# LS013B7DH03_TFT_Module.net
KiCad netlist of a schematic drawn in EAGLE
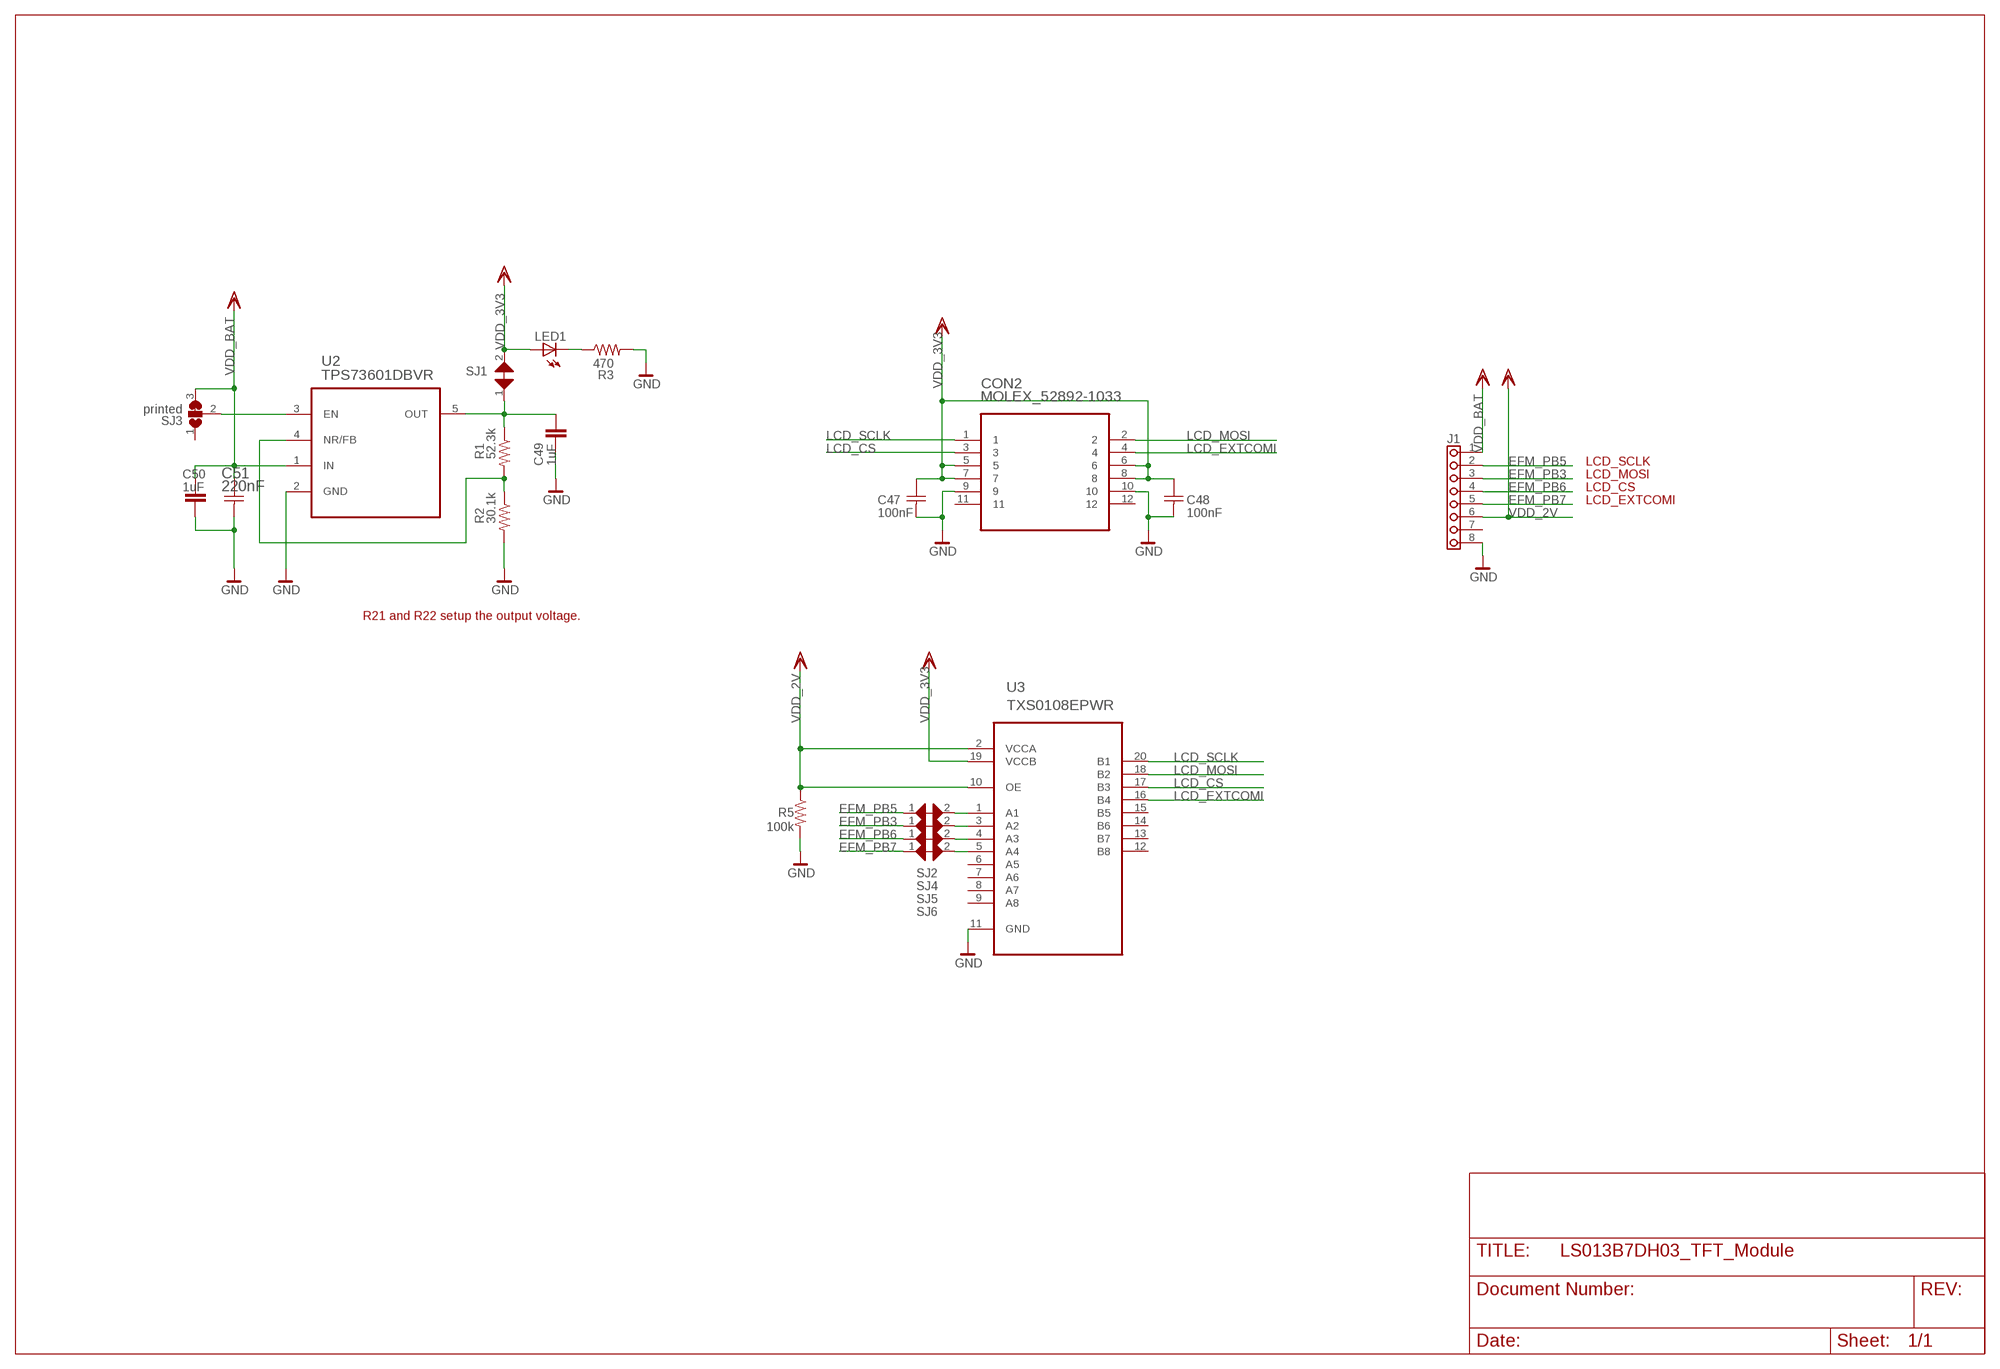
[diagram p0: schematic, sheet 1]

(export (version "E")
  (design (tool "Eeschema 10.0.6"))
  (components
    (comp (ref "C47")
      (value "100nF")
      (footprint "eagle-import:CAPC1005X60N")
      (libsource (lib "eagle-import") (part "CAP_GRM15"))
    )
    (comp (ref "C48")
      (value "100nF")
      (footprint "eagle-import:CAPC1005X60N")
      (libsource (lib "eagle-import") (part "CAP_GRM15"))
    )
    (comp (ref "C49")
      (value "1uF")
      (footprint "eagle-import:0603")
      (libsource (lib "eagle-import") (part "CAP-SMD0603"))
    )
    (comp (ref "C50")
      (value "1uF")
      (footprint "eagle-import:0603")
      (libsource (lib "eagle-import") (part "CAP-SMD0603"))
    )
    (comp (ref "C51")
      (value "220nF")
      (footprint "eagle-import:CAPC1005X60N")
      (libsource (lib "eagle-import") (part "CAP_GRM15"))
    )
    (comp (ref "CON2")
      (value "MOLEX_52892-1033")
      (footprint "eagle-import:MOLEX_52892-1095")
      (libsource (lib "eagle-import") (part "MOLEX_52892-1033_FPC"))
    )
    (comp (ref "J1")
      (value "PIN8S")
      (footprint "eagle-import:PIN8S")
      (libsource (lib "eagle-import") (part "PIN8S"))
    )
    (comp (ref "LED1")
      (value "LED0603")
      (footprint "eagle-import:LED-0603")
      (libsource (lib "eagle-import") (part "LED0603"))
    )
    (comp (ref "R1")
      (value "52.3k")
      (footprint "eagle-import:R0402")
      (libsource (lib "eagle-import") (part "R-US_R0402"))
    )
    (comp (ref "R2")
      (value "30.1k")
      (footprint "eagle-import:R0402")
      (libsource (lib "eagle-import") (part "R-US_R0402"))
    )
    (comp (ref "R3")
      (value "470")
      (footprint "eagle-import:R0402")
      (libsource (lib "eagle-import") (part "R-US_R0402"))
    )
    (comp (ref "R5")
      (value "100k")
      (footprint "eagle-import:R0402")
      (libsource (lib "eagle-import") (part "R-US_R0402"))
    )
    (comp (ref "SJ1")
      (value "printed")
      (footprint "eagle-import:JUMPER_SMD_MICRO_SHORT")
      (libsource (lib "eagle-import") (part "JUMPER_SMD_MICRO_SHORT"))
    )
    (comp (ref "SJ2")
      (value "printed")
      (footprint "eagle-import:JUMPER_SMD_MICRO_SHORT")
      (libsource (lib "eagle-import") (part "JUMPER_SMD_MICRO_SHORT"))
    )
    (comp (ref "SJ3")
      (value "printed")
      (footprint "eagle-import:JUMPER_SMD_SJ2A")
      (libsource (lib "eagle-import") (part "JUMPER_SMD_3A"))
    )
    (comp (ref "SJ4")
      (value "printed")
      (footprint "eagle-import:JUMPER_SMD_MICRO_SHORT")
      (libsource (lib "eagle-import") (part "JUMPER_SMD_MICRO_SHORT"))
    )
    (comp (ref "SJ5")
      (value "printed")
      (footprint "eagle-import:JUMPER_SMD_MICRO_SHORT")
      (libsource (lib "eagle-import") (part "JUMPER_SMD_MICRO_SHORT"))
    )
    (comp (ref "SJ6")
      (value "printed")
      (footprint "eagle-import:JUMPER_SMD_MICRO_SHORT")
      (libsource (lib "eagle-import") (part "JUMPER_SMD_MICRO_SHORT"))
    )
    (comp (ref "U2")
      (value "TPS73601DBVR")
      (footprint "eagle-import:SOT95P280X145-5N")
      (libsource (lib "eagle-import") (part "TPS73601DBVR"))
    )
    (comp (ref "U3")
      (value "TXS0108EPWR")
      (footprint "eagle-import:SOP65P640X120-20N")
      (libsource (lib "eagle-import") (part "TXB0108PWR"))
    )
  )
  (nets
    (net (code "1") (name "/EFM_PB3") (class "Default")
      (node (ref "J1") (pin "3") (pinfunction "3_3") (pintype "passive"))
      (node (ref "SJ4") (pin "1") (pinfunction "1_1") (pintype "passive"))
    )
    (net (code "2") (name "/EFM_PB5") (class "Default")
      (node (ref "J1") (pin "2") (pinfunction "2_2") (pintype "passive"))
      (node (ref "SJ2") (pin "1") (pinfunction "1_1") (pintype "passive"))
    )
    (net (code "3") (name "/EFM_PB6") (class "Default")
      (node (ref "J1") (pin "4") (pinfunction "4_4") (pintype "passive"))
      (node (ref "SJ5") (pin "1") (pinfunction "1_1") (pintype "passive"))
    )
    (net (code "4") (name "/EFM_PB7") (class "Default")
      (node (ref "J1") (pin "5") (pinfunction "5_5") (pintype "passive"))
      (node (ref "SJ6") (pin "1") (pinfunction "1_1") (pintype "passive"))
    )
    (net (code "5") (name "/LCD_CS") (class "Default")
      (node (ref "CON2") (pin "3") (pinfunction "3_3") (pintype "passive"))
      (node (ref "U3") (pin "17") (pinfunction "B3_17") (pintype "bidirectional"))
    )
    (net (code "6") (name "/LCD_EXTCOMI") (class "Default")
      (node (ref "CON2") (pin "4") (pinfunction "4_4") (pintype "passive"))
      (node (ref "U3") (pin "16") (pinfunction "B4_16") (pintype "bidirectional"))
    )
    (net (code "7") (name "/LCD_MOSI") (class "Default")
      (node (ref "CON2") (pin "2") (pinfunction "2_2") (pintype "passive"))
      (node (ref "U3") (pin "18") (pinfunction "B2_18") (pintype "bidirectional"))
    )
    (net (code "8") (name "/LCD_SCLK") (class "Default")
      (node (ref "CON2") (pin "1") (pinfunction "1_1") (pintype "passive"))
      (node (ref "U3") (pin "20") (pinfunction "B1_20") (pintype "bidirectional"))
    )
    (net (code "9") (name "GND") (class "Default")
      (node (ref "C47") (pin "2") (pinfunction "C2_2") (pintype "passive"))
      (node (ref "C48") (pin "2") (pinfunction "C2_2") (pintype "passive"))
      (node (ref "C49") (pin "1") (pinfunction "1_1") (pintype "passive"))
      (node (ref "C50") (pin "1") (pinfunction "1_1") (pintype "passive"))
      (node (ref "C51") (pin "2") (pinfunction "C2_2") (pintype "passive"))
      (node (ref "CON2") (pin "10") (pinfunction "10_10") (pintype "passive"))
      (node (ref "CON2") (pin "9") (pinfunction "9_9") (pintype "passive"))
      (node (ref "J1") (pin "8") (pinfunction "8_8") (pintype "passive"))
      (node (ref "R2") (pin "2") (pinfunction "2_2") (pintype "passive"))
      (node (ref "R3") (pin "2") (pinfunction "2_2") (pintype "passive"))
      (node (ref "R5") (pin "2") (pinfunction "2_2") (pintype "passive"))
      (node (ref "U2") (pin "2") (pinfunction "GND_2") (pintype "passive"))
      (node (ref "U3") (pin "11") (pinfunction "GND_11") (pintype "passive"))
    )
    (net (code "10") (name "Net-(LED1-PadC)") (class "Default")
      (node (ref "LED1") (pin "C") (pinfunction "C_C") (pintype "passive"))
      (node (ref "R3") (pin "1") (pinfunction "1_1") (pintype "passive"))
    )
    (net (code "11") (name "Net-(U2-EN)") (class "Default")
      (node (ref "SJ3") (pin "2") (pinfunction "2_2") (pintype "passive"))
      (node (ref "U2") (pin "3") (pinfunction "EN_3") (pintype "input"))
    )
    (net (code "12") (name "Net-(U2-NR{slash}FB)") (class "Default")
      (node (ref "R1") (pin "2") (pinfunction "2_2") (pintype "passive"))
      (node (ref "R2") (pin "1") (pinfunction "1_1") (pintype "passive"))
      (node (ref "U2") (pin "4") (pinfunction "NR/FB_4") (pintype "input"))
    )
    (net (code "13") (name "Net-(U2-OUT)") (class "Default")
      (node (ref "C49") (pin "2") (pinfunction "2_2") (pintype "passive"))
      (node (ref "R1") (pin "1") (pinfunction "1_1") (pintype "passive"))
      (node (ref "SJ1") (pin "1") (pinfunction "1_1") (pintype "passive"))
      (node (ref "U2") (pin "5") (pinfunction "OUT_5") (pintype "power_in"))
    )
    (net (code "14") (name "Net-(U3-A1)") (class "Default")
      (node (ref "SJ2") (pin "2") (pinfunction "2_2") (pintype "passive"))
      (node (ref "U3") (pin "1") (pinfunction "A1_1") (pintype "bidirectional"))
    )
    (net (code "15") (name "Net-(U3-A2)") (class "Default")
      (node (ref "SJ4") (pin "2") (pinfunction "2_2") (pintype "passive"))
      (node (ref "U3") (pin "3") (pinfunction "A2_3") (pintype "bidirectional"))
    )
    (net (code "16") (name "Net-(U3-A3)") (class "Default")
      (node (ref "SJ5") (pin "2") (pinfunction "2_2") (pintype "passive"))
      (node (ref "U3") (pin "4") (pinfunction "A3_4") (pintype "bidirectional"))
    )
    (net (code "17") (name "Net-(U3-A4)") (class "Default")
      (node (ref "SJ6") (pin "2") (pinfunction "2_2") (pintype "passive"))
      (node (ref "U3") (pin "5") (pinfunction "A4_5") (pintype "bidirectional"))
    )
    (net (code "18") (name "VDD_2V") (class "Default")
      (node (ref "J1") (pin "6") (pinfunction "6_6") (pintype "passive"))
      (node (ref "R5") (pin "1") (pinfunction "1_1") (pintype "passive"))
      (node (ref "U3") (pin "10") (pinfunction "OE_10") (pintype "input"))
      (node (ref "U3") (pin "2") (pinfunction "VCCA_2") (pintype "power_in"))
    )
    (net (code "19") (name "VDD_3V3") (class "Default")
      (node (ref "C47") (pin "1") (pinfunction "C1_1") (pintype "passive"))
      (node (ref "C48") (pin "1") (pinfunction "C1_1") (pintype "passive"))
      (node (ref "CON2") (pin "5") (pinfunction "5_5") (pintype "passive"))
      (node (ref "CON2") (pin "6") (pinfunction "6_6") (pintype "passive"))
      (node (ref "CON2") (pin "7") (pinfunction "7_7") (pintype "passive"))
      (node (ref "CON2") (pin "8") (pinfunction "8_8") (pintype "passive"))
      (node (ref "LED1") (pin "A") (pinfunction "A_A") (pintype "passive"))
      (node (ref "SJ1") (pin "2") (pinfunction "2_2") (pintype "passive"))
      (node (ref "U3") (pin "19") (pinfunction "VCCB_19") (pintype "power_in"))
    )
    (net (code "20") (name "VDD_BAT") (class "Default")
      (node (ref "C50") (pin "2") (pinfunction "2_2") (pintype "passive"))
      (node (ref "C51") (pin "1") (pinfunction "C1_1") (pintype "passive"))
      (node (ref "J1") (pin "1") (pinfunction "1_1") (pintype "passive"))
      (node (ref "SJ3") (pin "3") (pinfunction "3_3") (pintype "passive"))
      (node (ref "U2") (pin "1") (pinfunction "IN_1") (pintype "power_in"))
    )
    (net (code "21") (name "unconnected-(CON2-Pad11)") (class "Default")
      (node (ref "CON2") (pin "11") (pinfunction "11_11") (pintype "passive"))
    )
    (net (code "22") (name "unconnected-(CON2-Pad12)") (class "Default")
      (node (ref "CON2") (pin "12") (pinfunction "12_12") (pintype "passive"))
    )
    (net (code "23") (name "unconnected-(J1-Pad7)") (class "Default")
      (node (ref "J1") (pin "7") (pinfunction "7_7") (pintype "passive"))
    )
    (net (code "24") (name "unconnected-(SJ3-Pad1)") (class "Default")
      (node (ref "SJ3") (pin "1") (pinfunction "1_1") (pintype "passive"))
    )
    (net (code "25") (name "unconnected-(U3-A5-Pad6)") (class "Default")
      (node (ref "U3") (pin "6") (pinfunction "A5_6") (pintype "bidirectional"))
    )
    (net (code "26") (name "unconnected-(U3-A6-Pad7)") (class "Default")
      (node (ref "U3") (pin "7") (pinfunction "A6_7") (pintype "bidirectional"))
    )
    (net (code "27") (name "unconnected-(U3-A7-Pad8)") (class "Default")
      (node (ref "U3") (pin "8") (pinfunction "A7_8") (pintype "bidirectional"))
    )
    (net (code "28") (name "unconnected-(U3-A8-Pad9)") (class "Default")
      (node (ref "U3") (pin "9") (pinfunction "A8_9") (pintype "bidirectional"))
    )
    (net (code "29") (name "unconnected-(U3-B5-Pad15)") (class "Default")
      (node (ref "U3") (pin "15") (pinfunction "B5_15") (pintype "bidirectional"))
    )
    (net (code "30") (name "unconnected-(U3-B6-Pad14)") (class "Default")
      (node (ref "U3") (pin "14") (pinfunction "B6_14") (pintype "bidirectional"))
    )
    (net (code "31") (name "unconnected-(U3-B7-Pad13)") (class "Default")
      (node (ref "U3") (pin "13") (pinfunction "B7_13") (pintype "bidirectional"))
    )
    (net (code "32") (name "unconnected-(U3-B8-Pad12)") (class "Default")
      (node (ref "U3") (pin "12") (pinfunction "B8_12") (pintype "bidirectional"))
    )
  )
)
